# Nu_Capsule.net
KiCad netlist of a schematic drawn in EAGLE
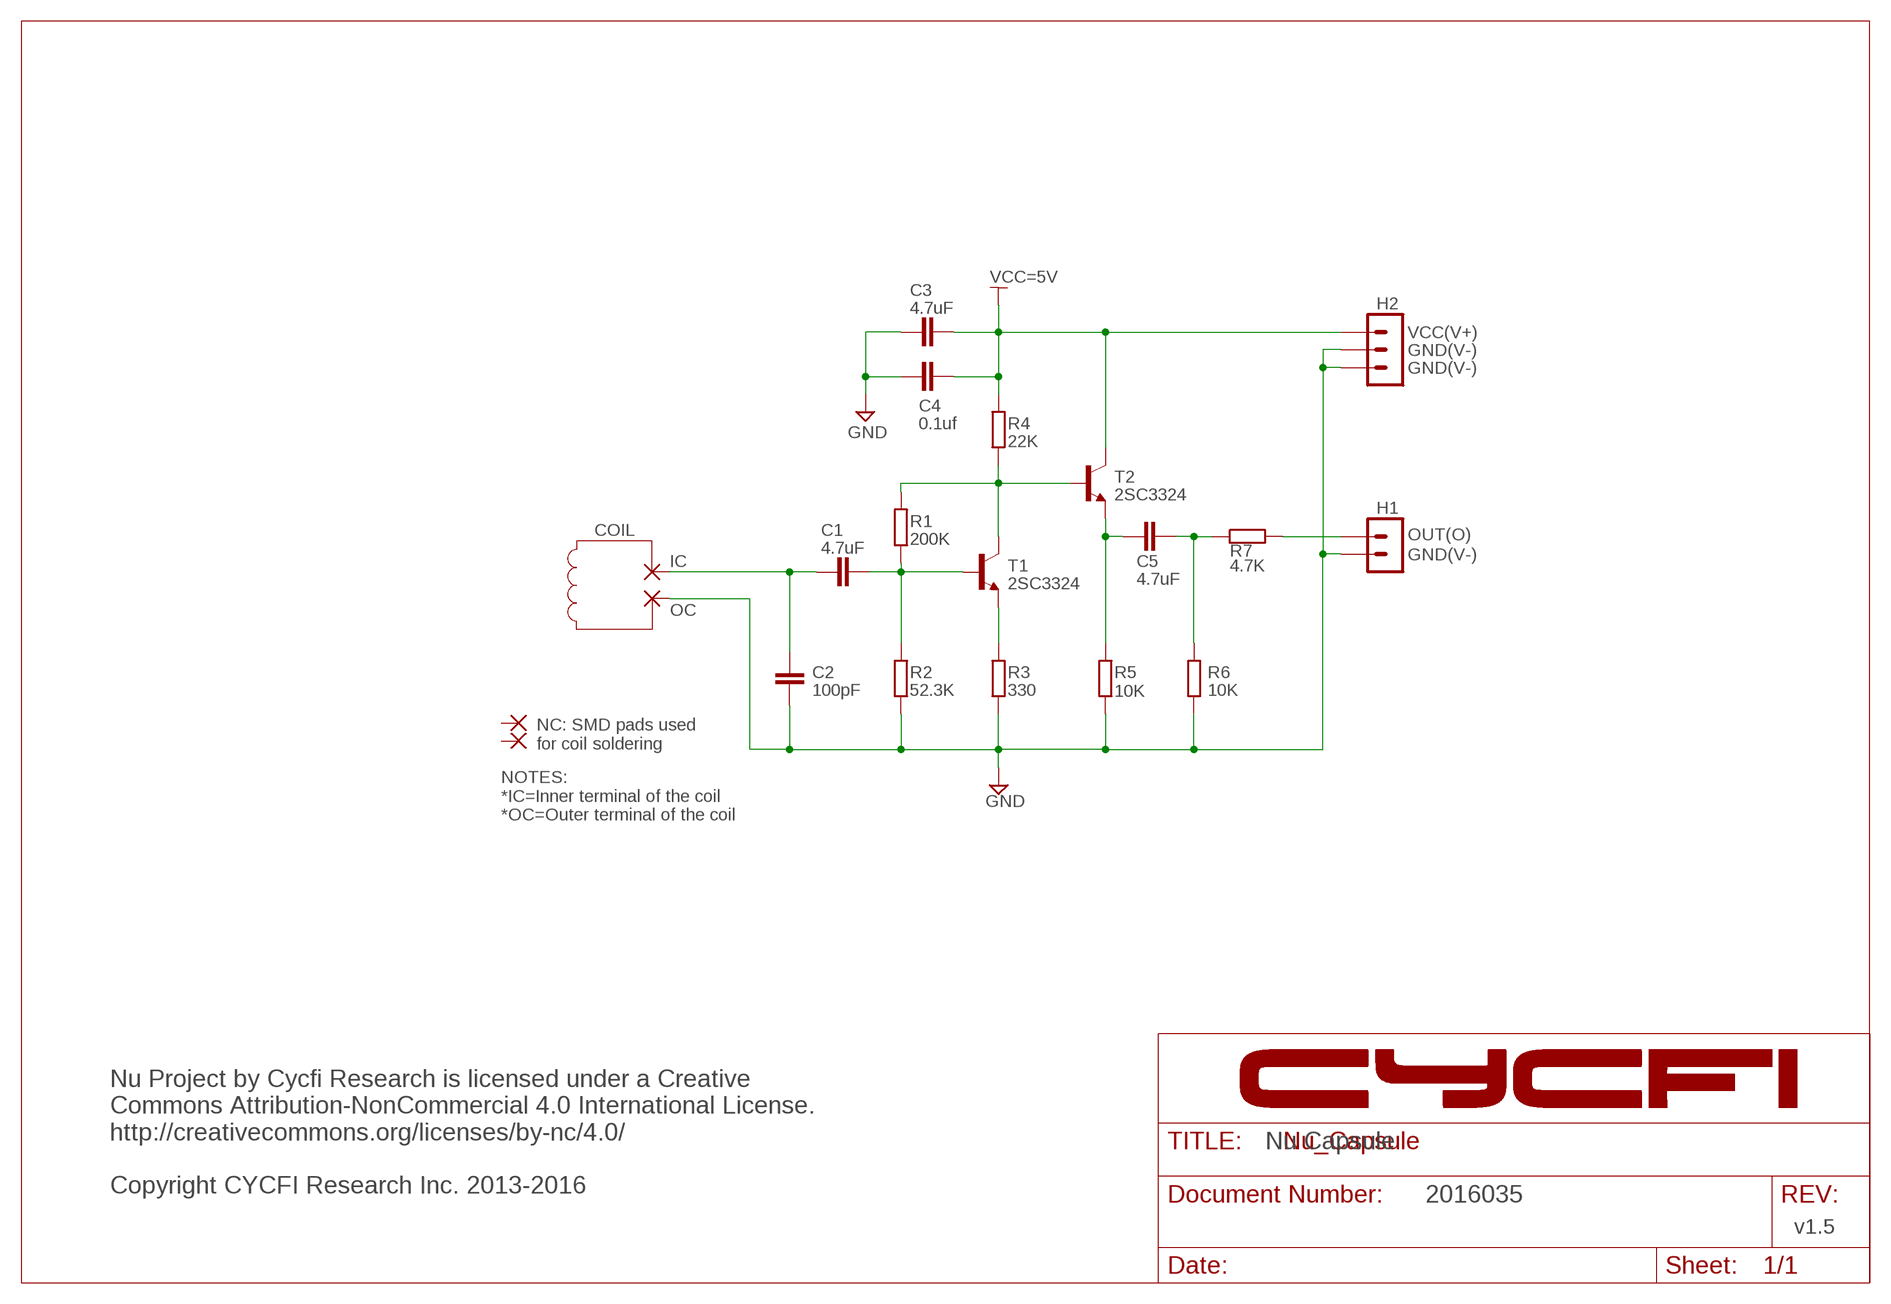
[diagram p0: schematic, sheet 1]

(export (version "E")
  (design (tool "Eeschema 10.0.6"))
  (components
    (comp (ref "C1")
      (value "4.7uF")
      (footprint "eagle-import:C0805")
      (libsource (lib "eagle-import") (part "C-EUC0805"))
    )
    (comp (ref "C2")
      (value "100pF")
      (footprint "eagle-import:C0603")
      (libsource (lib "eagle-import") (part "C-EUC0603"))
    )
    (comp (ref "C3")
      (value "4.7uF")
      (footprint "eagle-import:C0603")
      (libsource (lib "eagle-import") (part "C-EUC0603"))
    )
    (comp (ref "C4")
      (value "0.1uf")
      (footprint "eagle-import:C0603")
      (libsource (lib "eagle-import") (part "C-EUC0603"))
    )
    (comp (ref "C5")
      (value "4.7uF")
      (footprint "eagle-import:C0805")
      (libsource (lib "eagle-import") (part "C-EUC0805"))
    )
    (comp (ref "H1")
      (value "2P-2MM-TH-MALE")
      (footprint "eagle-import:2P-2MM-TH")
      (libsource (lib "eagle-import") (part "2P-2MM-TH-MALE"))
    )
    (comp (ref "H2")
      (value "3P-2MM-TH-MALE")
      (footprint "eagle-import:3P-2MM-TH")
      (libsource (lib "eagle-import") (part "3P-2MM-TH-MALE"))
    )
    (comp (ref "PAD6")
      (value "WIREPADSMD1,27-254")
      (footprint "eagle-import:SMD1,27-2,54")
      (libsource (lib "eagle-import") (part "WIREPADSMD1,27-254"))
    )
    (comp (ref "PAD7")
      (value "WIREPADSMD1,27-254")
      (footprint "eagle-import:SMD1,27-2,54")
      (libsource (lib "eagle-import") (part "WIREPADSMD1,27-254"))
    )
    (comp (ref "PAD18")
      (value "WIREPADSMD1,27-254")
      (footprint "eagle-import:SMD1,27-2,54")
      (libsource (lib "eagle-import") (part "WIREPADSMD1,27-254"))
    )
    (comp (ref "PAD19")
      (value "WIREPADSMD1,27-254")
      (footprint "eagle-import:SMD1,27-2,54")
      (libsource (lib "eagle-import") (part "WIREPADSMD1,27-254"))
    )
    (comp (ref "R1")
      (value "200K")
      (footprint "eagle-import:R0603")
      (libsource (lib "eagle-import") (part "R-EU_R0603"))
    )
    (comp (ref "R2")
      (value "52.3K")
      (footprint "eagle-import:R0805")
      (libsource (lib "eagle-import") (part "R-EU_R0805"))
    )
    (comp (ref "R3")
      (value "330")
      (footprint "eagle-import:R0402")
      (libsource (lib "eagle-import") (part "R-EU_R0402"))
    )
    (comp (ref "R4")
      (value "22K")
      (footprint "eagle-import:R0402")
      (libsource (lib "eagle-import") (part "R-EU_R0402"))
    )
    (comp (ref "R5")
      (value "10K")
      (footprint "eagle-import:R0402")
      (libsource (lib "eagle-import") (part "R-EU_R0402"))
    )
    (comp (ref "R6")
      (value "10K")
      (footprint "eagle-import:R0402")
      (libsource (lib "eagle-import") (part "R-EU_R0402"))
    )
    (comp (ref "R7")
      (value "4.7K")
      (footprint "eagle-import:R0402")
      (libsource (lib "eagle-import") (part "R-EU_R0402"))
    )
    (comp (ref "T1")
      (value "2SC3324")
      (footprint "eagle-import:SOT23")
      (libsource (lib "eagle-import") (part "BC846"))
    )
    (comp (ref "T2")
      (value "2SC3324")
      (footprint "eagle-import:SOT23")
      (libsource (lib "eagle-import") (part "BC846"))
    )
  )
  (nets
    (net (code "1") (name "GND") (class "Default")
      (node (ref "C2") (pin "1") (pinfunction "1_1") (pintype "passive"))
      (node (ref "C3") (pin "1") (pinfunction "1_1") (pintype "passive"))
      (node (ref "C4") (pin "1") (pinfunction "1_1") (pintype "passive"))
      (node (ref "H1") (pin "P$2") (pinfunction "2_P$2") (pintype "passive"))
      (node (ref "H2") (pin "P$2") (pinfunction "2_P$2") (pintype "passive"))
      (node (ref "H2") (pin "P$3") (pinfunction "3_P$3") (pintype "passive"))
      (node (ref "PAD7") (pin "1") (pinfunction "P_1") (pintype "passive"))
      (node (ref "R2") (pin "1") (pinfunction "1_1") (pintype "passive"))
      (node (ref "R3") (pin "1") (pinfunction "1_1") (pintype "passive"))
      (node (ref "R5") (pin "1") (pinfunction "1_1") (pintype "passive"))
      (node (ref "R6") (pin "1") (pinfunction "1_1") (pintype "passive"))
    )
    (net (code "2") (name "Net-(C5-Pad1)") (class "Default")
      (node (ref "C5") (pin "1") (pinfunction "1_1") (pintype "passive"))
      (node (ref "R6") (pin "2") (pinfunction "2_2") (pintype "passive"))
      (node (ref "R7") (pin "1") (pinfunction "1_1") (pintype "passive"))
    )
    (net (code "3") (name "Net-(H1-1)") (class "Default")
      (node (ref "H1") (pin "P$1") (pinfunction "1_P$1") (pintype "passive"))
      (node (ref "R7") (pin "2") (pinfunction "2_2") (pintype "passive"))
    )
    (net (code "4") (name "Net-(H2-1)") (class "Default")
      (node (ref "C3") (pin "2") (pinfunction "2_2") (pintype "passive"))
      (node (ref "C4") (pin "2") (pinfunction "2_2") (pintype "passive"))
      (node (ref "H2") (pin "P$1") (pinfunction "1_P$1") (pintype "passive"))
      (node (ref "R4") (pin "2") (pinfunction "2_2") (pintype "passive"))
      (node (ref "T2") (pin "3") (pinfunction "C_3") (pintype "passive"))
    )
    (net (code "5") (name "Net-(PAD6-P)") (class "Default")
      (node (ref "C1") (pin "1") (pinfunction "1_1") (pintype "passive"))
      (node (ref "C2") (pin "2") (pinfunction "2_2") (pintype "passive"))
      (node (ref "PAD6") (pin "1") (pinfunction "P_1") (pintype "passive"))
    )
    (net (code "6") (name "Net-(T1-B)") (class "Default")
      (node (ref "C1") (pin "2") (pinfunction "2_2") (pintype "passive"))
      (node (ref "R1") (pin "1") (pinfunction "1_1") (pintype "passive"))
      (node (ref "R2") (pin "2") (pinfunction "2_2") (pintype "passive"))
      (node (ref "T1") (pin "1") (pinfunction "B_1") (pintype "passive"))
    )
    (net (code "7") (name "Net-(T1-C)") (class "Default")
      (node (ref "R1") (pin "2") (pinfunction "2_2") (pintype "passive"))
      (node (ref "R4") (pin "1") (pinfunction "1_1") (pintype "passive"))
      (node (ref "T1") (pin "3") (pinfunction "C_3") (pintype "passive"))
      (node (ref "T2") (pin "1") (pinfunction "B_1") (pintype "passive"))
    )
    (net (code "8") (name "Net-(T1-E)") (class "Default")
      (node (ref "R3") (pin "2") (pinfunction "2_2") (pintype "passive"))
      (node (ref "T1") (pin "2") (pinfunction "E_2") (pintype "passive"))
    )
    (net (code "9") (name "Net-(T2-E)") (class "Default")
      (node (ref "C5") (pin "2") (pinfunction "2_2") (pintype "passive"))
      (node (ref "R5") (pin "2") (pinfunction "2_2") (pintype "passive"))
      (node (ref "T2") (pin "2") (pinfunction "E_2") (pintype "passive"))
    )
    (net (code "10") (name "unconnected-(PAD18-P-Pad1)") (class "Default")
      (node (ref "PAD18") (pin "1") (pinfunction "P_1") (pintype "passive"))
    )
    (net (code "11") (name "unconnected-(PAD19-P-Pad1)") (class "Default")
      (node (ref "PAD19") (pin "1") (pinfunction "P_1") (pintype "passive"))
    )
  )
)
